# board1.net
KiCad netlist of a schematic drawn in EAGLE
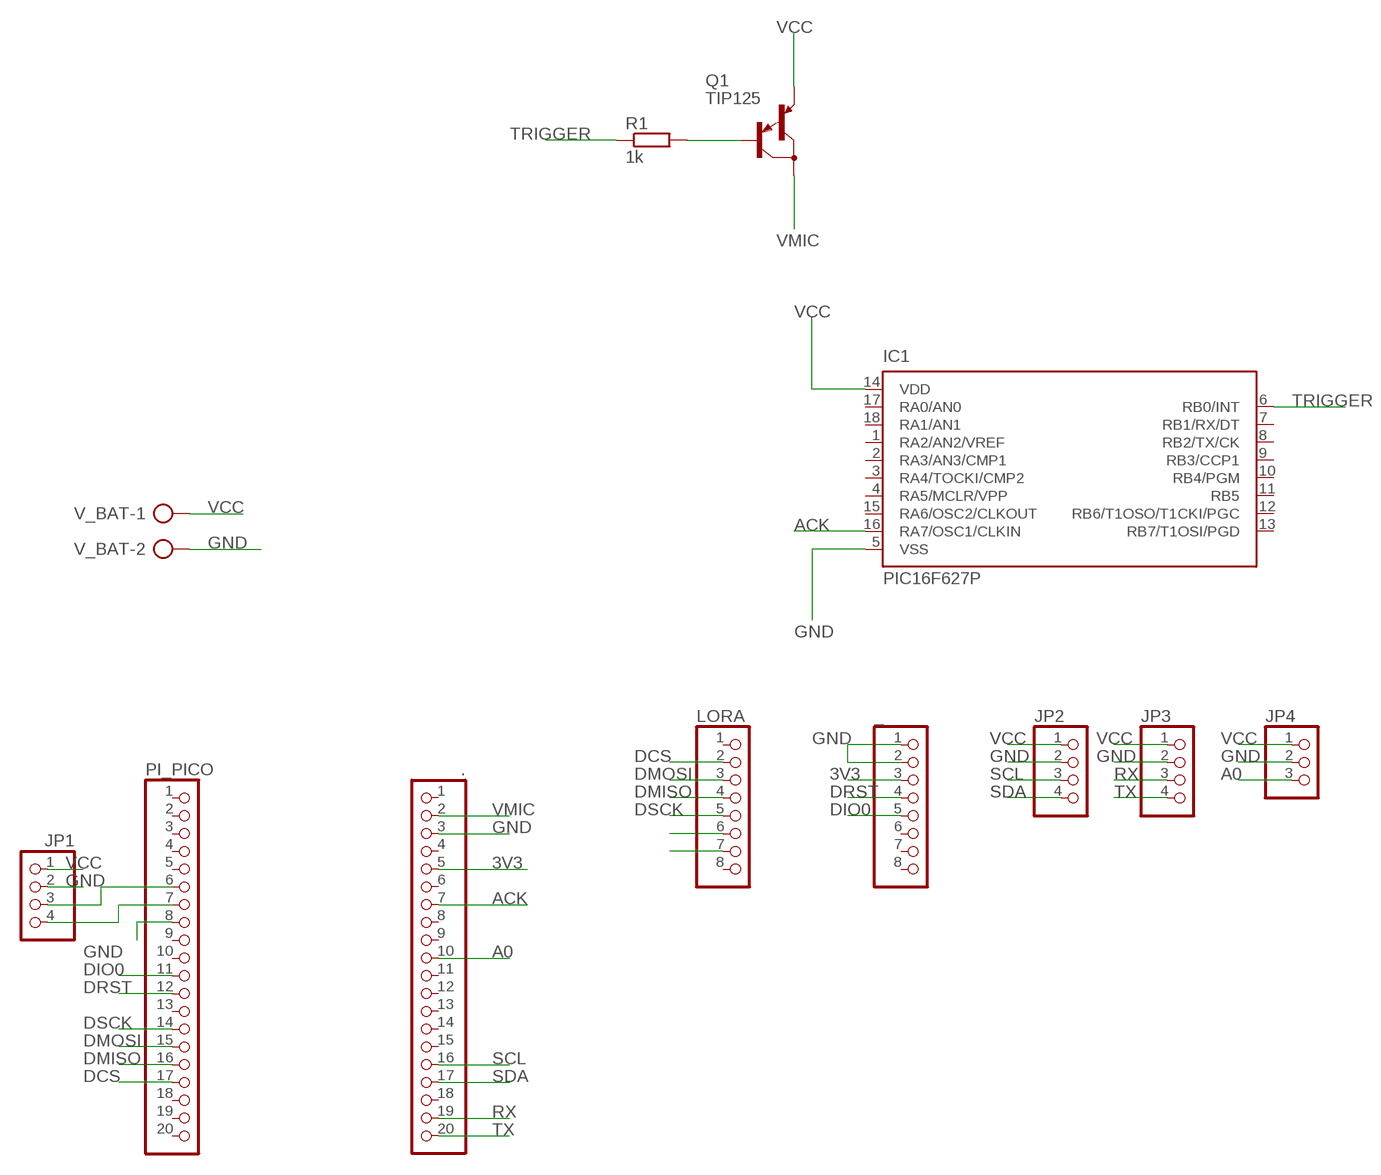
[diagram p0: schematic, sheet 1]

(export (version "E")
  (design (tool "Eeschema 10.0.6"))
  (components
    (comp (ref ".")
      (value "PINHD-1X20")
      (footprint "eagle-import:1X20")
      (libsource (lib "eagle-import") (part "PINHD-1X20"))
    )
    (comp (ref "IC1")
      (value "PIC16F627P")
      (footprint "eagle-import:DIL18")
      (fields (field (name "MF") "MICROCHIP") (field (name "MPN") "PIC16F627-04/P"))
      (libsource (lib "eagle-import") (part "PIC16F62P7"))
    )
    (comp (ref "JP1")
      (value "PINHD-1X4")
      (footprint "eagle-import:1X04")
      (libsource (lib "eagle-import") (part "PINHD-1X4"))
    )
    (comp (ref "JP2")
      (value "PINHD-1X4")
      (footprint "eagle-import:1X04")
      (libsource (lib "eagle-import") (part "PINHD-1X4"))
    )
    (comp (ref "JP3")
      (value "PINHD-1X4")
      (footprint "eagle-import:1X04")
      (libsource (lib "eagle-import") (part "PINHD-1X4"))
    )
    (comp (ref "JP4")
      (value "PINHD-1X3")
      (footprint "eagle-import:1X03")
      (libsource (lib "eagle-import") (part "PINHD-1X3"))
    )
    (comp (ref "LORA")
      (value "PINHD-1X8")
      (footprint "eagle-import:1X08")
      (libsource (lib "eagle-import") (part "PINHD-1X8"))
    )
    (comp (ref "PI_PICO")
      (value "PINHD-1X20")
      (footprint "eagle-import:1X20")
      (libsource (lib "eagle-import") (part "PINHD-1X20"))
    )
    (comp (ref "Q1")
      (value "TIP125")
      (footprint "eagle-import:TO220")
      (libsource (lib "eagle-import") (part "TIP125"))
    )
    (comp (ref "R1")
      (value "1k")
      (footprint "eagle-import:0411_15")
      (libsource (lib "eagle-import") (part "R-EU_0411/15"))
    )
    (comp (ref "V_BAT")
      (value "AK500/2-H")
      (footprint "eagle-import:AK500_2-H")
      (libsource (lib "eagle-import") (part "AK500/2-H"))
    )
    (comp (ref "_")
      (value "PINHD-1X8")
      (footprint "eagle-import:1X08")
      (libsource (lib "eagle-import") (part "PINHD-1X8"))
    )
  )
  (nets
    (net (code "1") (name "/3V3") (class "Default")
      (node (ref ".") (pin "5") (pinfunction "5_5") (pintype "passive"))
      (node (ref "_") (pin "3") (pinfunction "3_3") (pintype "passive"))
    )
    (net (code "2") (name "/A0") (class "Default")
      (node (ref ".") (pin "10") (pinfunction "10_10") (pintype "passive"))
      (node (ref "JP4") (pin "3") (pinfunction "3_3") (pintype "passive"))
    )
    (net (code "3") (name "/ACK") (class "Default")
      (node (ref ".") (pin "7") (pinfunction "7_7") (pintype "passive"))
      (node (ref "IC1") (pin "16") (pinfunction "RA7/OSC1/CLKIN_16") (pintype "bidirectional"))
    )
    (net (code "4") (name "/DCS") (class "Default")
      (node (ref "LORA") (pin "2") (pinfunction "2_2") (pintype "passive"))
      (node (ref "PI_PICO") (pin "17") (pinfunction "17_17") (pintype "passive"))
    )
    (net (code "5") (name "/DIO0") (class "Default")
      (node (ref "PI_PICO") (pin "11") (pinfunction "11_11") (pintype "passive"))
      (node (ref "_") (pin "5") (pinfunction "5_5") (pintype "passive"))
    )
    (net (code "6") (name "/DMISO") (class "Default")
      (node (ref "LORA") (pin "4") (pinfunction "4_4") (pintype "passive"))
      (node (ref "PI_PICO") (pin "16") (pinfunction "16_16") (pintype "passive"))
    )
    (net (code "7") (name "/DMOSI") (class "Default")
      (node (ref "LORA") (pin "3") (pinfunction "3_3") (pintype "passive"))
      (node (ref "PI_PICO") (pin "15") (pinfunction "15_15") (pintype "passive"))
    )
    (net (code "8") (name "/DRST") (class "Default")
      (node (ref "PI_PICO") (pin "12") (pinfunction "12_12") (pintype "passive"))
      (node (ref "_") (pin "4") (pinfunction "4_4") (pintype "passive"))
    )
    (net (code "9") (name "/DSCK") (class "Default")
      (node (ref "LORA") (pin "5") (pinfunction "5_5") (pintype "passive"))
      (node (ref "PI_PICO") (pin "14") (pinfunction "14_14") (pintype "passive"))
    )
    (net (code "10") (name "/GND") (class "Default")
      (node (ref ".") (pin "3") (pinfunction "3_3") (pintype "passive"))
      (node (ref "IC1") (pin "5") (pinfunction "VSS_5") (pintype "power_in"))
      (node (ref "JP1") (pin "2") (pinfunction "2_2") (pintype "passive"))
      (node (ref "JP2") (pin "2") (pinfunction "2_2") (pintype "passive"))
      (node (ref "JP3") (pin "2") (pinfunction "2_2") (pintype "passive"))
      (node (ref "JP4") (pin "2") (pinfunction "2_2") (pintype "passive"))
      (node (ref "PI_PICO") (pin "8") (pinfunction "8_8") (pintype "passive"))
      (node (ref "V_BAT") (pin "2") (pinfunction "KL_2") (pintype "passive"))
      (node (ref "_") (pin "1") (pinfunction "1_1") (pintype "passive"))
      (node (ref "_") (pin "2") (pinfunction "2_2") (pintype "passive"))
    )
    (net (code "11") (name "/RX") (class "Default")
      (node (ref ".") (pin "19") (pinfunction "19_19") (pintype "passive"))
      (node (ref "JP3") (pin "3") (pinfunction "3_3") (pintype "passive"))
    )
    (net (code "12") (name "/SCL") (class "Default")
      (node (ref ".") (pin "16") (pinfunction "16_16") (pintype "passive"))
      (node (ref "JP2") (pin "3") (pinfunction "3_3") (pintype "passive"))
    )
    (net (code "13") (name "/SDA") (class "Default")
      (node (ref ".") (pin "17") (pinfunction "17_17") (pintype "passive"))
      (node (ref "JP2") (pin "4") (pinfunction "4_4") (pintype "passive"))
    )
    (net (code "14") (name "/TRIGGER") (class "Default")
      (node (ref "IC1") (pin "6") (pinfunction "RB0/INT_6") (pintype "bidirectional"))
      (node (ref "R1") (pin "1") (pinfunction "1_1") (pintype "passive"))
    )
    (net (code "15") (name "/TX") (class "Default")
      (node (ref ".") (pin "20") (pinfunction "20_20") (pintype "passive"))
      (node (ref "JP3") (pin "4") (pinfunction "4_4") (pintype "passive"))
    )
    (net (code "16") (name "/VCC") (class "Default")
      (node (ref "IC1") (pin "14") (pinfunction "VDD_14") (pintype "power_in"))
      (node (ref "JP1") (pin "1") (pinfunction "1_1") (pintype "passive"))
      (node (ref "JP2") (pin "1") (pinfunction "1_1") (pintype "passive"))
      (node (ref "JP3") (pin "1") (pinfunction "1_1") (pintype "passive"))
      (node (ref "JP4") (pin "1") (pinfunction "1_1") (pintype "passive"))
      (node (ref "Q1") (pin "3") (pinfunction "E_3") (pintype "passive"))
      (node (ref "V_BAT") (pin "1") (pinfunction "KL_1") (pintype "passive"))
    )
    (net (code "17") (name "/VMIC") (class "Default")
      (node (ref ".") (pin "2") (pinfunction "2_2") (pintype "passive"))
      (node (ref "Q1") (pin "2") (pinfunction "C_2") (pintype "passive"))
    )
    (net (code "18") (name "Net-(JP1-Pad3)") (class "Default")
      (node (ref "JP1") (pin "3") (pinfunction "3_3") (pintype "passive"))
      (node (ref "PI_PICO") (pin "6") (pinfunction "6_6") (pintype "passive"))
    )
    (net (code "19") (name "Net-(JP1-Pad4)") (class "Default")
      (node (ref "JP1") (pin "4") (pinfunction "4_4") (pintype "passive"))
      (node (ref "PI_PICO") (pin "7") (pinfunction "7_7") (pintype "passive"))
    )
    (net (code "20") (name "Net-(Q1-B)") (class "Default")
      (node (ref "Q1") (pin "1") (pinfunction "B_1") (pintype "passive"))
      (node (ref "R1") (pin "2") (pinfunction "2_2") (pintype "passive"))
    )
    (net (code "21") (name "unconnected-(.-Pad1)") (class "Default")
      (node (ref ".") (pin "1") (pinfunction "1_1") (pintype "passive"))
    )
    (net (code "22") (name "unconnected-(.-Pad4)") (class "Default")
      (node (ref ".") (pin "4") (pinfunction "4_4") (pintype "passive"))
    )
    (net (code "23") (name "unconnected-(.-Pad6)") (class "Default")
      (node (ref ".") (pin "6") (pinfunction "6_6") (pintype "passive"))
    )
    (net (code "24") (name "unconnected-(.-Pad8)") (class "Default")
      (node (ref ".") (pin "8") (pinfunction "8_8") (pintype "passive"))
    )
    (net (code "25") (name "unconnected-(.-Pad9)") (class "Default")
      (node (ref ".") (pin "9") (pinfunction "9_9") (pintype "passive"))
    )
    (net (code "26") (name "unconnected-(.-Pad11)") (class "Default")
      (node (ref ".") (pin "11") (pinfunction "11_11") (pintype "passive"))
    )
    (net (code "27") (name "unconnected-(.-Pad12)") (class "Default")
      (node (ref ".") (pin "12") (pinfunction "12_12") (pintype "passive"))
    )
    (net (code "28") (name "unconnected-(.-Pad13)") (class "Default")
      (node (ref ".") (pin "13") (pinfunction "13_13") (pintype "passive"))
    )
    (net (code "29") (name "unconnected-(.-Pad14)") (class "Default")
      (node (ref ".") (pin "14") (pinfunction "14_14") (pintype "passive"))
    )
    (net (code "30") (name "unconnected-(.-Pad15)") (class "Default")
      (node (ref ".") (pin "15") (pinfunction "15_15") (pintype "passive"))
    )
    (net (code "31") (name "unconnected-(.-Pad18)") (class "Default")
      (node (ref ".") (pin "18") (pinfunction "18_18") (pintype "passive"))
    )
    (net (code "32") (name "unconnected-(IC1-RA0{slash}AN0-Pad17)") (class "Default")
      (node (ref "IC1") (pin "17") (pinfunction "RA0/AN0_17") (pintype "bidirectional"))
    )
    (net (code "33") (name "unconnected-(IC1-RA1{slash}AN1-Pad18)") (class "Default")
      (node (ref "IC1") (pin "18") (pinfunction "RA1/AN1_18") (pintype "bidirectional"))
    )
    (net (code "34") (name "unconnected-(IC1-RA2{slash}AN2{slash}VREF-Pad1)") (class "Default")
      (node (ref "IC1") (pin "1") (pinfunction "RA2/AN2/VREF_1") (pintype "bidirectional"))
    )
    (net (code "35") (name "unconnected-(IC1-RA3{slash}AN3{slash}CMP1-Pad2)") (class "Default")
      (node (ref "IC1") (pin "2") (pinfunction "RA3/AN3/CMP1_2") (pintype "bidirectional"))
    )
    (net (code "36") (name "unconnected-(IC1-RA4{slash}TOCKI{slash}CMP2-Pad3)") (class "Default")
      (node (ref "IC1") (pin "3") (pinfunction "RA4/TOCKI/CMP2_3") (pintype "bidirectional"))
    )
    (net (code "37") (name "unconnected-(IC1-RA5{slash}MCLR{slash}VPP-Pad4)") (class "Default")
      (node (ref "IC1") (pin "4") (pinfunction "RA5/MCLR/VPP_4") (pintype "bidirectional"))
    )
    (net (code "38") (name "unconnected-(IC1-RA6{slash}OSC2{slash}CLKOUT-Pad15)") (class "Default")
      (node (ref "IC1") (pin "15") (pinfunction "RA6/OSC2/CLKOUT_15") (pintype "bidirectional"))
    )
    (net (code "39") (name "unconnected-(IC1-RB1{slash}RX{slash}DT-Pad7)") (class "Default")
      (node (ref "IC1") (pin "7") (pinfunction "RB1/RX/DT_7") (pintype "bidirectional"))
    )
    (net (code "40") (name "unconnected-(IC1-RB2{slash}TX{slash}CK-Pad8)") (class "Default")
      (node (ref "IC1") (pin "8") (pinfunction "RB2/TX/CK_8") (pintype "bidirectional"))
    )
    (net (code "41") (name "unconnected-(IC1-RB3{slash}CCP1-Pad9)") (class "Default")
      (node (ref "IC1") (pin "9") (pinfunction "RB3/CCP1_9") (pintype "bidirectional"))
    )
    (net (code "42") (name "unconnected-(IC1-RB4{slash}PGM-Pad10)") (class "Default")
      (node (ref "IC1") (pin "10") (pinfunction "RB4/PGM_10") (pintype "bidirectional"))
    )
    (net (code "43") (name "unconnected-(IC1-RB5-Pad11)") (class "Default")
      (node (ref "IC1") (pin "11") (pinfunction "RB5_11") (pintype "bidirectional"))
    )
    (net (code "44") (name "unconnected-(IC1-RB6{slash}T1OSO{slash}T1CKI{slash}PGC-Pad12)") (class "Default")
      (node (ref "IC1") (pin "12") (pinfunction "RB6/T1OSO/T1CKI/PGC_12") (pintype "bidirectional"))
    )
    (net (code "45") (name "unconnected-(IC1-RB7{slash}T1OSI{slash}PGD-Pad13)") (class "Default")
      (node (ref "IC1") (pin "13") (pinfunction "RB7/T1OSI/PGD_13") (pintype "bidirectional"))
    )
    (net (code "46") (name "unconnected-(LORA-Pad1)") (class "Default")
      (node (ref "LORA") (pin "1") (pinfunction "1_1") (pintype "passive"))
    )
    (net (code "47") (name "unconnected-(LORA-Pad6)") (class "Default")
      (node (ref "LORA") (pin "6") (pinfunction "6_6") (pintype "passive"))
    )
    (net (code "48") (name "unconnected-(LORA-Pad7)") (class "Default")
      (node (ref "LORA") (pin "7") (pinfunction "7_7") (pintype "passive"))
    )
    (net (code "49") (name "unconnected-(LORA-Pad8)") (class "Default")
      (node (ref "LORA") (pin "8") (pinfunction "8_8") (pintype "passive"))
    )
    (net (code "50") (name "unconnected-(PI_PICO-Pad1)") (class "Default")
      (node (ref "PI_PICO") (pin "1") (pinfunction "1_1") (pintype "passive"))
    )
    (net (code "51") (name "unconnected-(PI_PICO-Pad2)") (class "Default")
      (node (ref "PI_PICO") (pin "2") (pinfunction "2_2") (pintype "passive"))
    )
    (net (code "52") (name "unconnected-(PI_PICO-Pad3)") (class "Default")
      (node (ref "PI_PICO") (pin "3") (pinfunction "3_3") (pintype "passive"))
    )
    (net (code "53") (name "unconnected-(PI_PICO-Pad4)") (class "Default")
      (node (ref "PI_PICO") (pin "4") (pinfunction "4_4") (pintype "passive"))
    )
    (net (code "54") (name "unconnected-(PI_PICO-Pad5)") (class "Default")
      (node (ref "PI_PICO") (pin "5") (pinfunction "5_5") (pintype "passive"))
    )
    (net (code "55") (name "unconnected-(PI_PICO-Pad9)") (class "Default")
      (node (ref "PI_PICO") (pin "9") (pinfunction "9_9") (pintype "passive"))
    )
    (net (code "56") (name "unconnected-(PI_PICO-Pad10)") (class "Default")
      (node (ref "PI_PICO") (pin "10") (pinfunction "10_10") (pintype "passive"))
    )
    (net (code "57") (name "unconnected-(PI_PICO-Pad13)") (class "Default")
      (node (ref "PI_PICO") (pin "13") (pinfunction "13_13") (pintype "passive"))
    )
    (net (code "58") (name "unconnected-(PI_PICO-Pad18)") (class "Default")
      (node (ref "PI_PICO") (pin "18") (pinfunction "18_18") (pintype "passive"))
    )
    (net (code "59") (name "unconnected-(PI_PICO-Pad19)") (class "Default")
      (node (ref "PI_PICO") (pin "19") (pinfunction "19_19") (pintype "passive"))
    )
    (net (code "60") (name "unconnected-(PI_PICO-Pad20)") (class "Default")
      (node (ref "PI_PICO") (pin "20") (pinfunction "20_20") (pintype "passive"))
    )
    (net (code "61") (name "unconnected-(_-Pad6)") (class "Default")
      (node (ref "_") (pin "6") (pinfunction "6_6") (pintype "passive"))
    )
    (net (code "62") (name "unconnected-(_-Pad7)") (class "Default")
      (node (ref "_") (pin "7") (pinfunction "7_7") (pintype "passive"))
    )
    (net (code "63") (name "unconnected-(_-Pad8)") (class "Default")
      (node (ref "_") (pin "8") (pinfunction "8_8") (pintype "passive"))
    )
  )
)
